# E157_DP1.net
KiCad netlist of a schematic drawn in Altium Designer
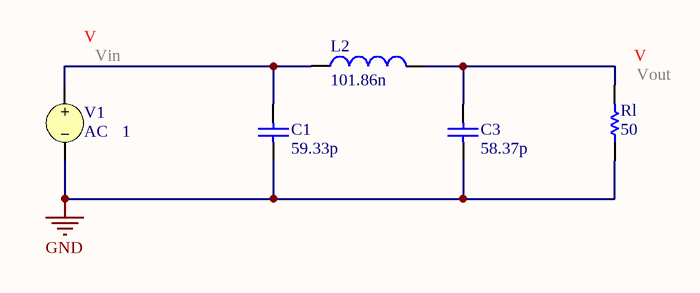
[diagram p0: E157 DP1.SchDoc]

(export (version "E")
  (design (tool "Eeschema 10.0.6"))
  (components
    (comp (ref "C1")
      (value "59.33p")
      (description "Capacitor")
      (libsource (lib "Simulation Generic Components") (part "Capacitor"))
    )
    (comp (ref "C3")
      (value "58.37p")
      (description "Capacitor")
      (libsource (lib "Simulation Generic Components") (part "Capacitor"))
    )
    (comp (ref "L2")
      (value "101.86n")
      (description "Inductor")
      (libsource (lib "Simulation Generic Components") (part "Inductor"))
    )
    (comp (ref "Rl")
      (value "50")
      (description "Resistor")
      (libsource (lib "Simulation Generic Components") (part "Resistor"))
    )
    (comp (ref "V1")
      (value "DC")
      (description "Voltage Source")
      (fields (field (name "AC MAGNITUDE") "1") (field (name "PUBLISHER") "Altium Limited"))
      (libsource (lib "Simulation Generic Components") (part "VSRC"))
    )
  )
  (nets
    (net (code "1") (name "GND") (class "Default")
      (node (ref "C1") (pin "1") (pinfunction "1_1") (pintype "passive"))
      (node (ref "C3") (pin "1") (pinfunction "1_1") (pintype "passive"))
      (node (ref "Rl") (pin "1") (pinfunction "1_1") (pintype "passive"))
      (node (ref "V1") (pin "2") (pinfunction "2_2") (pintype "passive"))
    )
    (net (code "2") (name "Net-(C1-Pad2)") (class "Default")
      (node (ref "C1") (pin "2") (pinfunction "2_2") (pintype "passive"))
      (node (ref "L2") (pin "1") (pinfunction "1_1") (pintype "passive"))
      (node (ref "V1") (pin "1") (pinfunction "1_1") (pintype "passive"))
    )
    (net (code "3") (name "Net-(C3-Pad2)") (class "Default")
      (node (ref "C3") (pin "2") (pinfunction "2_2") (pintype "passive"))
      (node (ref "L2") (pin "2") (pinfunction "2_2") (pintype "passive"))
      (node (ref "Rl") (pin "2") (pinfunction "2_2") (pintype "passive"))
    )
  )
)
